# Plant_friends_capsensor.net
KiCad netlist of a schematic drawn in EAGLE
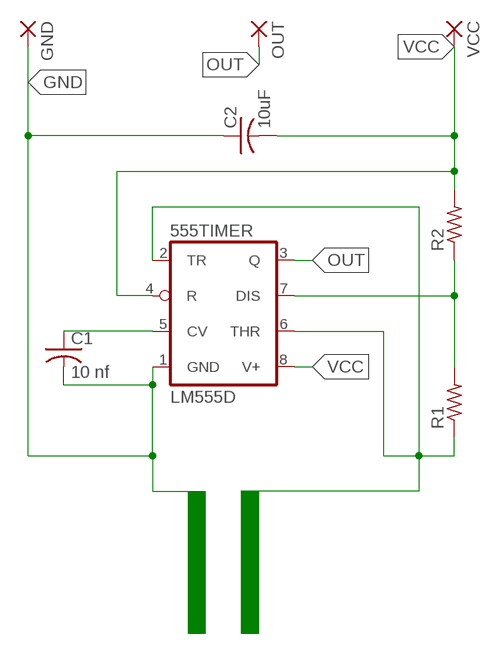
[diagram p0: schematic, sheet 1]

(export (version "E")
  (design (tool "Eeschema 10.0.6"))
  (components
    (comp (ref "555TIMER")
      (value "LM555D")
      (footprint "eagle-import:SO08")
      (libsource (lib "eagle-import") (part "555DLM"))
    )
    (comp (ref "C1")
      (value "10 nf")
      (footprint "eagle-import:C0805")
      (libsource (lib "eagle-import") (part "C-USC0805"))
    )
    (comp (ref "C2")
      (value "10uF")
      (footprint "eagle-import:C0805")
      (libsource (lib "eagle-import") (part "C-USC0805"))
    )
    (comp (ref "GND")
      (value "WIREPAD2,54/1,0")
      (footprint "eagle-import:2,54_1,0")
      (libsource (lib "eagle-import") (part "WIREPAD2,54/1,0"))
    )
    (comp (ref "OUT")
      (value "WIREPAD2,54/1,0")
      (footprint "eagle-import:2,54_1,0")
      (libsource (lib "eagle-import") (part "WIREPAD2,54/1,0"))
    )
    (comp (ref "R1")
      (value "R-US_R0805")
      (footprint "eagle-import:R0805")
      (libsource (lib "eagle-import") (part "R-US_R0805"))
    )
    (comp (ref "R2")
      (value "R-US_R0805")
      (footprint "eagle-import:R0805")
      (libsource (lib "eagle-import") (part "R-US_R0805"))
    )
    (comp (ref "VCC")
      (value "WIREPAD2,54/1,0")
      (footprint "eagle-import:2,54_1,0")
      (libsource (lib "eagle-import") (part "WIREPAD2,54/1,0"))
    )
  )
  (nets
    (net (code "1") (name "GND") (class "Default")
      (node (ref "555TIMER") (pin "1") (pinfunction "GND_1") (pintype "power_in"))
      (node (ref "C1") (pin "2") (pinfunction "2_2") (pintype "passive"))
      (node (ref "C2") (pin "1") (pinfunction "1_1") (pintype "passive"))
      (node (ref "GND") (pin "1") (pinfunction "P_1") (pintype "passive"))
    )
    (net (code "2") (name "Net-(555TIMER-CV)") (class "Default")
      (node (ref "555TIMER") (pin "5") (pinfunction "CV_5") (pintype "input"))
      (node (ref "C1") (pin "1") (pinfunction "1_1") (pintype "passive"))
    )
    (net (code "3") (name "Net-(555TIMER-DIS)") (class "Default")
      (node (ref "555TIMER") (pin "7") (pinfunction "DIS_7") (pintype "input"))
      (node (ref "R1") (pin "2") (pinfunction "2_2") (pintype "passive"))
      (node (ref "R2") (pin "1") (pinfunction "1_1") (pintype "passive"))
    )
    (net (code "4") (name "Net-(555TIMER-THR)") (class "Default")
      (node (ref "555TIMER") (pin "2") (pinfunction "TR_2") (pintype "input"))
      (node (ref "555TIMER") (pin "6") (pinfunction "THR_6") (pintype "input"))
      (node (ref "R1") (pin "1") (pinfunction "1_1") (pintype "passive"))
    )
    (net (code "5") (name "OUT") (class "Default")
      (node (ref "555TIMER") (pin "3") (pinfunction "Q_3") (pintype "output"))
      (node (ref "OUT") (pin "1") (pinfunction "P_1") (pintype "passive"))
    )
    (net (code "6") (name "VCC") (class "Default")
      (node (ref "555TIMER") (pin "4") (pinfunction "R_4") (pintype "input"))
      (node (ref "555TIMER") (pin "8") (pinfunction "V+_8") (pintype "power_in"))
      (node (ref "C2") (pin "2") (pinfunction "2_2") (pintype "passive"))
      (node (ref "R2") (pin "2") (pinfunction "2_2") (pintype "passive"))
      (node (ref "VCC") (pin "1") (pinfunction "P_1") (pintype "passive"))
    )
  )
)
